# ARDUINO.net
KiCad netlist of a schematic drawn in Altium Designer
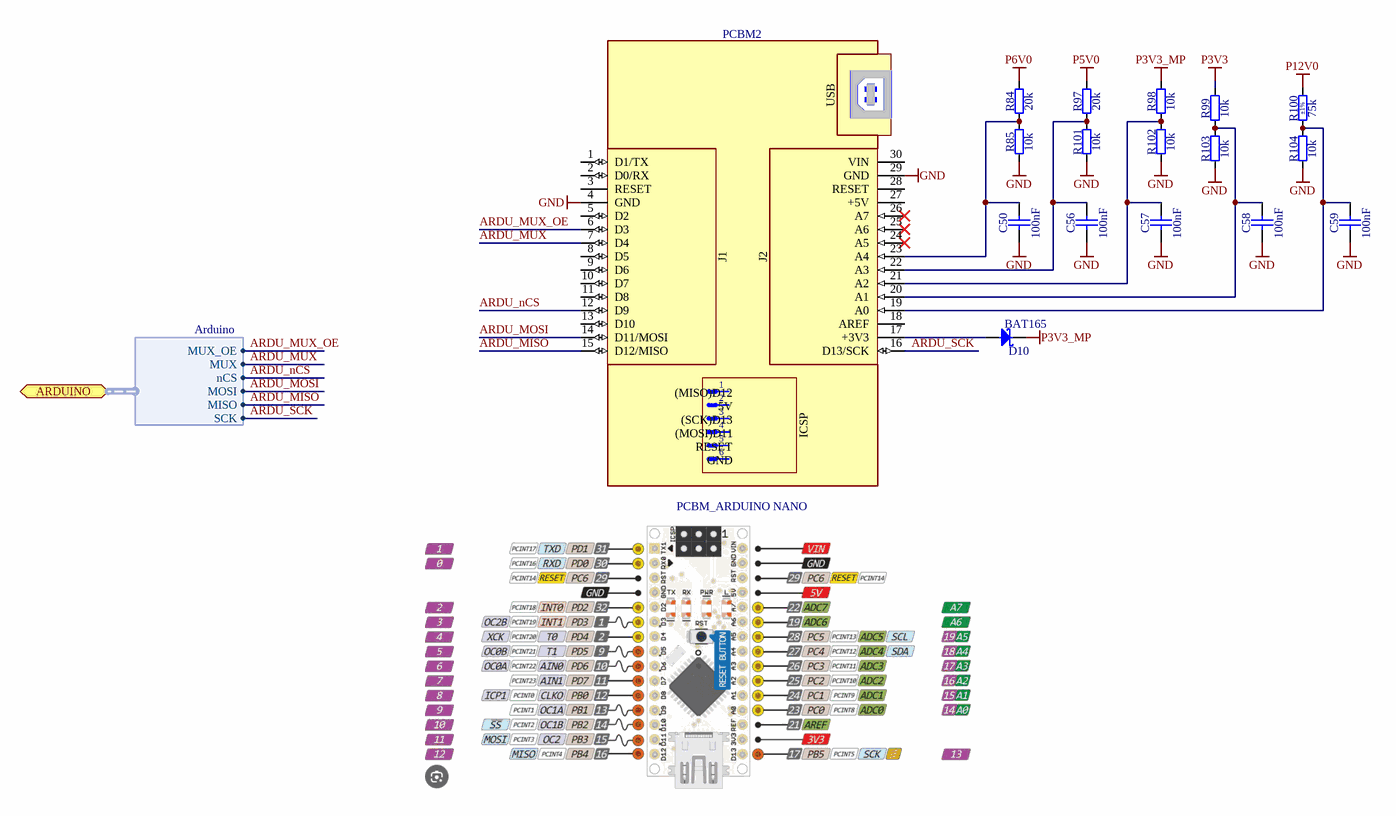
[diagram p0: ARDUINO.SchDoc]

(export (version "E")
  (design (tool "Eeschema 10.0.6"))
  (components
    (comp (ref "C50")
      (value "100nF")
      (footprint "CAPC1005X55N")
      (description "Non-polarised capacitor")
      (fields
        (field (name "PART NUMBER") "CC0402_100NF_16V_10%_X5R")
        (field (name "VOLTAGE") "16V")
        (field (name "AUTHOR") "CERN DEM JLC")
      )
      (libsource (lib "Capacitors") (part "Capacitor - non polarized"))
    )
    (comp (ref "C56")
      (value "100nF")
      (footprint "CAPC1005X55N")
      (description "Non-polarised capacitor")
      (fields
        (field (name "PART NUMBER") "CC0402_100NF_16V_10%_X5R")
        (field (name "VOLTAGE") "16V")
        (field (name "AUTHOR") "CERN DEM JLC")
      )
      (libsource (lib "Capacitors") (part "Capacitor - non polarized"))
    )
    (comp (ref "C57")
      (value "100nF")
      (footprint "CAPC1005X55N")
      (description "Non-polarised capacitor")
      (fields
        (field (name "PART NUMBER") "CC0402_100NF_16V_10%_X5R")
        (field (name "VOLTAGE") "16V")
        (field (name "AUTHOR") "CERN DEM JLC")
      )
      (libsource (lib "Capacitors") (part "Capacitor - non polarized"))
    )
    (comp (ref "C58")
      (value "100nF")
      (footprint "CAPC1005X55N")
      (description "Non-polarised capacitor")
      (fields
        (field (name "PART NUMBER") "CC0402_100NF_16V_10%_X5R")
        (field (name "VOLTAGE") "16V")
        (field (name "AUTHOR") "CERN DEM JLC")
      )
      (libsource (lib "Capacitors") (part "Capacitor - non polarized"))
    )
    (comp (ref "C59")
      (value "100nF")
      (footprint "CAPC1005X55N")
      (description "Non-polarised capacitor")
      (fields
        (field (name "PART NUMBER") "CC0402_100NF_16V_10%_X5R")
        (field (name "VOLTAGE") "16V")
        (field (name "AUTHOR") "CERN DEM JLC")
      )
      (libsource (lib "Capacitors") (part "Capacitor - non polarized"))
    )
    (comp (ref "D10")
      (value "BAT165")
      (footprint "SOD2512X110N")
      (description "Schottky Diode")
      (fields
        (field (name "VOLTAGE") "40V")
        (field (name "POWER") "750mA")
        (field (name "AUTHOR") "CERN DEM JLC")
      )
      (libsource (lib "ICs And Semiconductors") (part "Diode Schottky"))
    )
    (comp (ref "PCBM2")
      (value "PCBM_ARDUINO NANO")
      (footprint "PCBM_ARDUINO NANO_a")
      (description "Arduino NANO Printed Circuit Board Module")
      (fields
        (field (name "PART NUMBER") "PCBM_ARDUINO NANO_a")
        (field (name "MANUFACTURER") "ARDUINO")
        (field (name "AUTHOR") "CERN DEM HF")
      )
      (libsource (lib "ICs And Semiconductors") (part "PCBM_ARDUINO NANO_a"))
    )
    (comp (ref "R84")
      (value "20k")
      (footprint "RESC1608X55N")
      (description "Resistor - 1%")
      (fields
        (field (name "PART NUMBER") "R0603_20K_1%_0.1W_100PPM")
        (field (name "POWER") "0.1W")
        (field (name "AUTHOR") "CERN DEM JLC")
      )
      (libsource (lib "Resistors") (part "Resistor - 1%"))
    )
    (comp (ref "R85")
      (value "10k")
      (footprint "RESC1005X40N")
      (description "Resistor - 1%")
      (fields
        (field (name "PART NUMBER") "R0402_10K_1%_0.0625W_100PPM")
        (field (name "POWER") "0.0625W")
        (field (name "AUTHOR") "CERN DEM JLC")
      )
      (libsource (lib "Resistors") (part "Resistor - 1%"))
    )
    (comp (ref "R97")
      (value "20k")
      (footprint "RESC1608X55N")
      (description "Resistor - 1%")
      (fields
        (field (name "PART NUMBER") "R0603_20K_1%_0.1W_100PPM")
        (field (name "POWER") "0.1W")
        (field (name "AUTHOR") "CERN DEM JLC")
      )
      (libsource (lib "Resistors") (part "Resistor - 1%"))
    )
    (comp (ref "R98")
      (value "10k")
      (footprint "RESC1005X40N")
      (description "Resistor - 1%")
      (fields
        (field (name "PART NUMBER") "R0402_10K_1%_0.0625W_100PPM")
        (field (name "POWER") "0.0625W")
        (field (name "AUTHOR") "CERN DEM JLC")
      )
      (libsource (lib "Resistors") (part "Resistor - 1%"))
    )
    (comp (ref "R99")
      (value "10k")
      (footprint "RESC1005X40N")
      (description "Resistor - 1%")
      (fields
        (field (name "PART NUMBER") "R0402_10K_1%_0.0625W_100PPM")
        (field (name "POWER") "0.0625W")
        (field (name "AUTHOR") "CERN DEM JLC")
      )
      (libsource (lib "Resistors") (part "Resistor - 1%"))
    )
    (comp (ref "R100")
      (value "75k")
      (footprint "RESC1608X55N")
      (description "Resistor - 1%")
      (fields
        (field (name "TOLERANCE") "±1%")
        (field (name "PART NUMBER") "R0603_75K_1%_0.1W_100PPM")
        (field (name "POWER") "0.1W")
        (field (name "AUTHOR") "CERN DEM JLC")
      )
      (libsource (lib "Resistors") (part "Resistor - 1%"))
    )
    (comp (ref "R101")
      (value "10k")
      (footprint "RESC1005X40N")
      (description "Resistor - 1%")
      (fields
        (field (name "PART NUMBER") "R0402_10K_1%_0.0625W_100PPM")
        (field (name "POWER") "0.0625W")
        (field (name "AUTHOR") "CERN DEM JLC")
      )
      (libsource (lib "Resistors") (part "Resistor - 1%"))
    )
    (comp (ref "R102")
      (value "10k")
      (footprint "RESC1005X40N")
      (description "Resistor - 1%")
      (fields
        (field (name "PART NUMBER") "R0402_10K_1%_0.0625W_100PPM")
        (field (name "POWER") "0.0625W")
        (field (name "AUTHOR") "CERN DEM JLC")
      )
      (libsource (lib "Resistors") (part "Resistor - 1%"))
    )
    (comp (ref "R103")
      (value "10k")
      (footprint "RESC1005X40N")
      (description "Resistor - 1%")
      (fields
        (field (name "PART NUMBER") "R0402_10K_1%_0.0625W_100PPM")
        (field (name "POWER") "0.0625W")
        (field (name "AUTHOR") "CERN DEM JLC")
      )
      (libsource (lib "Resistors") (part "Resistor - 1%"))
    )
    (comp (ref "R104")
      (value "10k")
      (footprint "RESC1005X40N")
      (description "Resistor - 1%")
      (fields
        (field (name "PART NUMBER") "R0402_10K_1%_0.0625W_100PPM")
        (field (name "POWER") "0.0625W")
        (field (name "AUTHOR") "CERN DEM JLC")
      )
      (libsource (lib "Resistors") (part "Resistor - 1%"))
    )
  )
  (nets
    (net (code "2") (name "/ARDU_MISO") (class "Default")
      (node (ref "PCBM2") (pin "15") (pinfunction "D12/MISO_15") (pintype "bidirectional"))
    )
    (net (code "3") (name "/ARDU_MOSI") (class "Default")
      (node (ref "PCBM2") (pin "14") (pinfunction "D11/MOSI_14") (pintype "bidirectional"))
    )
    (net (code "4") (name "/ARDU_MUX") (class "Default")
      (node (ref "PCBM2") (pin "7") (pinfunction "D4_7") (pintype "bidirectional"))
    )
    (net (code "5") (name "/ARDU_MUX_OE") (class "Default")
      (node (ref "PCBM2") (pin "6") (pinfunction "D3_6") (pintype "bidirectional"))
    )
    (net (code "6") (name "/ARDU_SCK") (class "Default")
      (node (ref "PCBM2") (pin "16") (pinfunction "D13/SCK_16") (pintype "bidirectional"))
    )
    (net (code "7") (name "/ARDU_nCS") (class "Default")
      (node (ref "PCBM2") (pin "12") (pinfunction "D9_12") (pintype "bidirectional"))
    )
    (net (code "9") (name "GND") (class "Default")
      (node (ref "C50") (pin "1") (pinfunction "1_1") (pintype "passive"))
      (node (ref "C56") (pin "1") (pinfunction "1_1") (pintype "passive"))
      (node (ref "C57") (pin "1") (pinfunction "1_1") (pintype "passive"))
      (node (ref "C58") (pin "1") (pinfunction "1_1") (pintype "passive"))
      (node (ref "C59") (pin "1") (pinfunction "1_1") (pintype "passive"))
      (node (ref "PCBM2") (pin "29") (pinfunction "GND_29") (pintype "power_in"))
      (node (ref "PCBM2") (pin "4") (pinfunction "GND_4") (pintype "power_in"))
      (node (ref "R101") (pin "1") (pinfunction "1_1") (pintype "passive"))
      (node (ref "R102") (pin "1") (pinfunction "1_1") (pintype "passive"))
      (node (ref "R103") (pin "1") (pinfunction "1_1") (pintype "passive"))
      (node (ref "R104") (pin "1") (pinfunction "1_1") (pintype "passive"))
      (node (ref "R85") (pin "1") (pinfunction "1_1") (pintype "passive"))
    )
    (net (code "10") (name "Net-(D10-A)") (class "Default")
      (node (ref "D10") (pin "2") (pinfunction "A_2") (pintype "passive"))
      (node (ref "PCBM2") (pin "17") (pinfunction "+3V3_17") (pintype "power_in"))
    )
    (net (code "11") (name "Net-(PCBM2-A0)") (class "Default")
      (node (ref "C59") (pin "2") (pinfunction "2_2") (pintype "passive"))
      (node (ref "PCBM2") (pin "19") (pinfunction "A0_19") (pintype "input"))
      (node (ref "R100") (pin "1") (pinfunction "1_1") (pintype "passive"))
      (node (ref "R104") (pin "2") (pinfunction "2_2") (pintype "passive"))
    )
    (net (code "12") (name "Net-(PCBM2-A1)") (class "Default")
      (node (ref "C58") (pin "2") (pinfunction "2_2") (pintype "passive"))
      (node (ref "PCBM2") (pin "20") (pinfunction "A1_20") (pintype "input"))
      (node (ref "R103") (pin "2") (pinfunction "2_2") (pintype "passive"))
      (node (ref "R99") (pin "1") (pinfunction "1_1") (pintype "passive"))
    )
    (net (code "13") (name "Net-(PCBM2-A2)") (class "Default")
      (node (ref "C57") (pin "2") (pinfunction "2_2") (pintype "passive"))
      (node (ref "PCBM2") (pin "21") (pinfunction "A2_21") (pintype "input"))
      (node (ref "R102") (pin "2") (pinfunction "2_2") (pintype "passive"))
      (node (ref "R98") (pin "1") (pinfunction "1_1") (pintype "passive"))
    )
    (net (code "14") (name "Net-(PCBM2-A3)") (class "Default")
      (node (ref "C56") (pin "2") (pinfunction "2_2") (pintype "passive"))
      (node (ref "PCBM2") (pin "22") (pinfunction "A3_22") (pintype "input"))
      (node (ref "R101") (pin "2") (pinfunction "2_2") (pintype "passive"))
      (node (ref "R97") (pin "1") (pinfunction "1_1") (pintype "passive"))
    )
    (net (code "15") (name "Net-(PCBM2-A4)") (class "Default")
      (node (ref "C50") (pin "2") (pinfunction "2_2") (pintype "passive"))
      (node (ref "PCBM2") (pin "23") (pinfunction "A4_23") (pintype "input"))
      (node (ref "R84") (pin "1") (pinfunction "1_1") (pintype "passive"))
      (node (ref "R85") (pin "2") (pinfunction "2_2") (pintype "passive"))
    )
    (net (code "16") (name "P3V3") (class "Default")
      (node (ref "R99") (pin "2") (pinfunction "2_2") (pintype "passive"))
    )
    (net (code "17") (name "P3V3_MP") (class "Default")
      (node (ref "D10") (pin "1") (pinfunction "C_1") (pintype "passive"))
      (node (ref "R98") (pin "2") (pinfunction "2_2") (pintype "passive"))
    )
    (net (code "18") (name "P5V0") (class "Default")
      (node (ref "R97") (pin "2") (pinfunction "2_2") (pintype "passive"))
    )
    (net (code "19") (name "P6V0") (class "Default")
      (node (ref "R84") (pin "2") (pinfunction "2_2") (pintype "passive"))
    )
    (net (code "20") (name "P12V0") (class "Default")
      (node (ref "R100") (pin "2") (pinfunction "2_2") (pintype "passive"))
    )
    (net (code "21") (name "unconnected-(PCBM2-+5V-Pad27)") (class "Default")
      (node (ref "PCBM2") (pin "27") (pinfunction "+5V_27") (pintype "power_in"))
    )
    (net (code "22") (name "unconnected-(PCBM2-A5-Pad24)") (class "Default")
      (node (ref "PCBM2") (pin "24") (pinfunction "A5_24") (pintype "input+no_connect"))
    )
    (net (code "23") (name "unconnected-(PCBM2-A6-Pad25)") (class "Default")
      (node (ref "PCBM2") (pin "25") (pinfunction "A6_25") (pintype "input+no_connect"))
    )
    (net (code "24") (name "unconnected-(PCBM2-A7-Pad26)") (class "Default")
      (node (ref "PCBM2") (pin "26") (pinfunction "A7_26") (pintype "input+no_connect"))
    )
    (net (code "25") (name "unconnected-(PCBM2-AREF-Pad18)") (class "Default")
      (node (ref "PCBM2") (pin "18") (pinfunction "AREF_18") (pintype "passive"))
    )
    (net (code "26") (name "unconnected-(PCBM2-D0{slash}RX-Pad2)") (class "Default")
      (node (ref "PCBM2") (pin "2") (pinfunction "D0/RX_2") (pintype "bidirectional"))
    )
    (net (code "27") (name "unconnected-(PCBM2-D1{slash}TX-Pad1)") (class "Default")
      (node (ref "PCBM2") (pin "1") (pinfunction "D1/TX_1") (pintype "bidirectional"))
    )
    (net (code "28") (name "unconnected-(PCBM2-D2-Pad5)") (class "Default")
      (node (ref "PCBM2") (pin "5") (pinfunction "D2_5") (pintype "bidirectional"))
    )
    (net (code "29") (name "unconnected-(PCBM2-D5-Pad8)") (class "Default")
      (node (ref "PCBM2") (pin "8") (pinfunction "D5_8") (pintype "bidirectional"))
    )
    (net (code "30") (name "unconnected-(PCBM2-D6-Pad9)") (class "Default")
      (node (ref "PCBM2") (pin "9") (pinfunction "D6_9") (pintype "bidirectional"))
    )
    (net (code "31") (name "unconnected-(PCBM2-D7-Pad10)") (class "Default")
      (node (ref "PCBM2") (pin "10") (pinfunction "D7_10") (pintype "bidirectional"))
    )
    (net (code "32") (name "unconnected-(PCBM2-D8-Pad11)") (class "Default")
      (node (ref "PCBM2") (pin "11") (pinfunction "D8_11") (pintype "bidirectional"))
    )
    (net (code "33") (name "unconnected-(PCBM2-D10-Pad13)") (class "Default")
      (node (ref "PCBM2") (pin "13") (pinfunction "D10_13") (pintype "bidirectional"))
    )
    (net (code "34") (name "unconnected-(PCBM2-RESET-Pad3)") (class "Default")
      (node (ref "PCBM2") (pin "3") (pinfunction "RESET_3") (pintype "passive"))
    )
    (net (code "35") (name "unconnected-(PCBM2-RESET-Pad28)") (class "Default")
      (node (ref "PCBM2") (pin "28") (pinfunction "RESET_28") (pintype "passive"))
    )
    (net (code "36") (name "unconnected-(PCBM2-VIN-Pad30)") (class "Default")
      (node (ref "PCBM2") (pin "30") (pinfunction "VIN_30") (pintype "power_in"))
    )
  )
)
